# 04_8V_GENERATION.net
KiCad netlist of a schematic drawn in Altium Designer
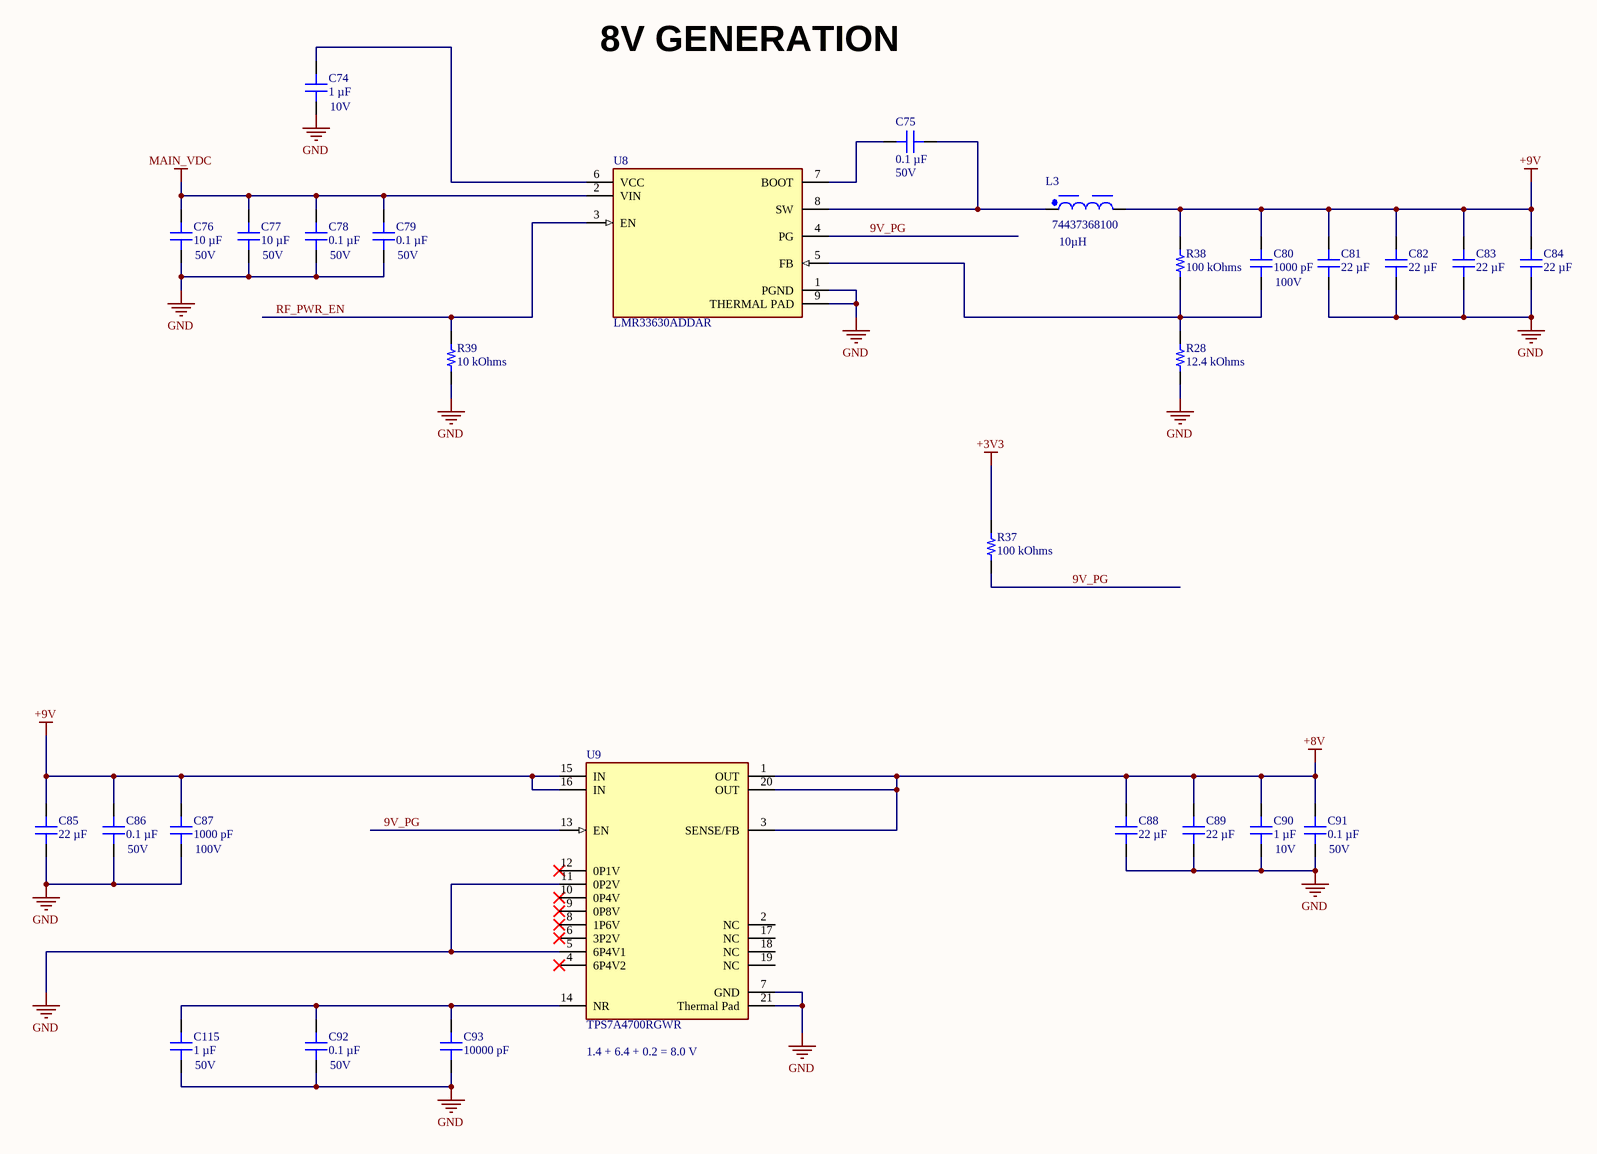
[diagram p0: 04_8V_GENERATION.SchDoc]

(export (version "E")
  (design (tool "Eeschema 10.0.6"))
  (components
    (comp (ref "C74")
      (value "1 µF")
      (footprint "CAP 0402_1005")
      (description "CAP CER 1UF 10V X7S 0402")
      (fields
        (field (name "PART NUMBER") "GRM155C71A105KE11D")
        (field (name "CAPACITANCE") "1 µF")
        (field (name "MANUFACTURER") "Murata Electronics")
        (field (name "VOLTAGE - RATED") "10V")
      )
      (libsource (lib "Celestial Altium Library - altium_library") (part "Capacitor"))
    )
    (comp (ref "C75")
      (value "0.1 µF")
      (footprint "CAP 0402_1005")
      (description "CAP CER 0.1UF 50V X7R 0402")
      (fields
        (field (name "PART NUMBER") "GCM155R71H104KE02J")
        (field (name "CAPACITANCE") "0.1 µF")
        (field (name "MANUFACTURER") "Murata Electronics")
        (field (name "VOLTAGE - RATED") "50V")
      )
      (libsource (lib "Celestial Altium Library - altium_library") (part "Capacitor"))
    )
    (comp (ref "C76")
      (value "10 µF")
      (footprint "CAP 1206_3216 - 0.8MM")
      (description "CAP CER 10UF 50V X7R 1206")
      (fields
        (field (name "PART NUMBER") "CL31B106KBHNNNE")
        (field (name "CAPACITANCE") "10 µF")
        (field (name "MANUFACTURER") "Samsung Electro-Mechanics")
        (field (name "VOLTAGE - RATED") "50V")
      )
      (libsource (lib "Celestial Altium Library - altium_library") (part "Capacitor"))
    )
    (comp (ref "C77")
      (value "10 µF")
      (footprint "CAP 1206_3216 - 0.8MM")
      (description "CAP CER 10UF 50V X7R 1206")
      (fields
        (field (name "PART NUMBER") "CL31B106KBHNNNE")
        (field (name "CAPACITANCE") "10 µF")
        (field (name "MANUFACTURER") "Samsung Electro-Mechanics")
        (field (name "VOLTAGE - RATED") "50V")
      )
      (libsource (lib "Celestial Altium Library - altium_library") (part "Capacitor"))
    )
    (comp (ref "C78")
      (value "0.1 µF")
      (footprint "CAP 0402_1005")
      (description "CAP CER 0.1UF 50V X7R 0402")
      (fields
        (field (name "PART NUMBER") "GCM155R71H104KE02J")
        (field (name "CAPACITANCE") "0.1 µF")
        (field (name "MANUFACTURER") "Murata Electronics")
        (field (name "VOLTAGE - RATED") "50V")
      )
      (libsource (lib "Celestial Altium Library - altium_library") (part "Capacitor"))
    )
    (comp (ref "C79")
      (value "0.1 µF")
      (footprint "CAP 0402_1005")
      (description "CAP CER 0.1UF 50V X7R 0402")
      (fields
        (field (name "PART NUMBER") "GCM155R71H104KE02J")
        (field (name "CAPACITANCE") "0.1 µF")
        (field (name "MANUFACTURER") "Murata Electronics")
        (field (name "VOLTAGE - RATED") "50V")
      )
      (libsource (lib "Celestial Altium Library - altium_library") (part "Capacitor"))
    )
    (comp (ref "C80")
      (value "1000 pF")
      (footprint "CAP 0402_1005")
      (description "CAP CER 1000PF 100V C0G/NP0 0402")
      (fields
        (field (name "PART NUMBER") "C0402H102J1GAC7867")
        (field (name "CAPACITANCE") "1000 pF")
        (field (name "MANUFACTURER") "KEMET")
        (field (name "VOLTAGE - RATED") "100V")
      )
      (libsource (lib "Celestial Altium Library - altium_library") (part "Capacitor"))
    )
    (comp (ref "C81")
      (value "22 µF")
      (footprint "CAP 0805_2012")
      (description "CAP CER 22UF 16V X5R 0805")
      (fields
        (field (name "PART NUMBER") "CL21A226KOQNNNE")
        (field (name "CAPACITANCE") "22 µF")
        (field (name "MANUFACTURER") "Samsung Electro-Mechanics")
      )
      (libsource (lib "Celestial Altium Library - altium_library") (part "Capacitor"))
    )
    (comp (ref "C82")
      (value "22 µF")
      (footprint "CAP 0805_2012")
      (description "CAP CER 22UF 16V X5R 0805")
      (fields
        (field (name "PART NUMBER") "CL21A226KOQNNNE")
        (field (name "CAPACITANCE") "22 µF")
        (field (name "MANUFACTURER") "Samsung Electro-Mechanics")
      )
      (libsource (lib "Celestial Altium Library - altium_library") (part "Capacitor"))
    )
    (comp (ref "C83")
      (value "22 µF")
      (footprint "CAP 0805_2012")
      (description "CAP CER 22UF 16V X5R 0805")
      (fields
        (field (name "PART NUMBER") "CL21A226KOQNNNE")
        (field (name "CAPACITANCE") "22 µF")
        (field (name "MANUFACTURER") "Samsung Electro-Mechanics")
      )
      (libsource (lib "Celestial Altium Library - altium_library") (part "Capacitor"))
    )
    (comp (ref "C84")
      (value "22 µF")
      (footprint "CAP 0805_2012")
      (description "CAP CER 22UF 16V X5R 0805")
      (fields
        (field (name "PART NUMBER") "CL21A226KOQNNNE")
        (field (name "CAPACITANCE") "22 µF")
        (field (name "MANUFACTURER") "Samsung Electro-Mechanics")
      )
      (libsource (lib "Celestial Altium Library - altium_library") (part "Capacitor"))
    )
    (comp (ref "C85")
      (value "22 µF")
      (footprint "CAP 0805_2012")
      (description "CAP CER 22UF 16V X5R 0805")
      (fields
        (field (name "PART NUMBER") "CL21A226KOQNNNE")
        (field (name "CAPACITANCE") "22 µF")
        (field (name "MANUFACTURER") "Samsung Electro-Mechanics")
      )
      (libsource (lib "Celestial Altium Library - altium_library") (part "Capacitor"))
    )
    (comp (ref "C86")
      (value "0.1 µF")
      (footprint "CAP 0402_1005")
      (description "CAP CER 0.1UF 50V X7R 0402")
      (fields
        (field (name "PART NUMBER") "GCM155R71H104KE02J")
        (field (name "CAPACITANCE") "0.1 µF")
        (field (name "MANUFACTURER") "Murata Electronics")
        (field (name "VOLTAGE - RATED") "50V")
      )
      (libsource (lib "Celestial Altium Library - altium_library") (part "Capacitor"))
    )
    (comp (ref "C87")
      (value "1000 pF")
      (footprint "CAP 0402_1005")
      (description "CAP CER 1000PF 100V C0G/NP0 0402")
      (fields
        (field (name "PART NUMBER") "C0402H102J1GAC7867")
        (field (name "CAPACITANCE") "1000 pF")
        (field (name "MANUFACTURER") "KEMET")
        (field (name "VOLTAGE - RATED") "100V")
      )
      (libsource (lib "Celestial Altium Library - altium_library") (part "Capacitor"))
    )
    (comp (ref "C88")
      (value "22 µF")
      (footprint "CAP 0805_2012")
      (description "CAP CER 22UF 16V X5R 0805")
      (fields
        (field (name "PART NUMBER") "CL21A226KOQNNNE")
        (field (name "CAPACITANCE") "22 µF")
        (field (name "MANUFACTURER") "Samsung Electro-Mechanics")
      )
      (libsource (lib "Celestial Altium Library - altium_library") (part "Capacitor"))
    )
    (comp (ref "C89")
      (value "22 µF")
      (footprint "CAP 0805_2012")
      (description "CAP CER 22UF 16V X5R 0805")
      (fields
        (field (name "PART NUMBER") "CL21A226KOQNNNE")
        (field (name "CAPACITANCE") "22 µF")
        (field (name "MANUFACTURER") "Samsung Electro-Mechanics")
      )
      (libsource (lib "Celestial Altium Library - altium_library") (part "Capacitor"))
    )
    (comp (ref "C90")
      (value "1 µF")
      (footprint "CAP 0402_1005")
      (description "CAP CER 1UF 10V X7S 0402")
      (fields
        (field (name "PART NUMBER") "GRM155C71A105KE11D")
        (field (name "CAPACITANCE") "1 µF")
        (field (name "MANUFACTURER") "Murata Electronics")
        (field (name "VOLTAGE - RATED") "10V")
      )
      (libsource (lib "Celestial Altium Library - altium_library") (part "Capacitor"))
    )
    (comp (ref "C91")
      (value "0.1 µF")
      (footprint "CAP 0402_1005")
      (description "CAP CER 0.1UF 50V X7R 0402")
      (fields
        (field (name "PART NUMBER") "GCM155R71H104KE02J")
        (field (name "CAPACITANCE") "0.1 µF")
        (field (name "MANUFACTURER") "Murata Electronics")
        (field (name "VOLTAGE - RATED") "50V")
      )
      (libsource (lib "Celestial Altium Library - altium_library") (part "Capacitor"))
    )
    (comp (ref "C92")
      (value "0.1 µF")
      (footprint "CAP 0402_1005")
      (description "CAP CER 0.1UF 50V X7R 0402")
      (fields
        (field (name "PART NUMBER") "GCM155R71H104KE02J")
        (field (name "CAPACITANCE") "0.1 µF")
        (field (name "MANUFACTURER") "Murata Electronics")
        (field (name "VOLTAGE - RATED") "50V")
      )
      (libsource (lib "Celestial Altium Library - altium_library") (part "Capacitor"))
    )
    (comp (ref "C93")
      (value "10000 pF")
      (footprint "CAP 0402_1005")
      (description "CAP CER 10000PF 50V X7R 0402")
      (fields
        (field (name "PART NUMBER") "AC0402KPX7R9BB103")
        (field (name "CAPACITANCE") "10000 pF")
        (field (name "MANUFACTURER") "Yageo")
      )
      (libsource (lib "Celestial Altium Library - altium_library") (part "Capacitor"))
    )
    (comp (ref "C115")
      (value "1 µF")
      (footprint "CAP 0805_2012")
      (description "CAP CER 1UF 50V X7R 0805")
      (fields
        (field (name "PART NUMBER") "UMF212B7105KGHT")
        (field (name "CAPACITANCE") "1 µF")
        (field (name "MANUFACTURER") "Taiyo Yuden")
        (field (name "VOLTAGE - RATED") "50V")
      )
      (libsource (lib "Celestial Altium Library - altium_library") (part "Capacitor"))
    )
    (comp (ref "L3")
      (value "74437368100")
      (footprint "WE-LHMI_1040")
      (description "We-lhmi; 10000NH; Composite Iron Multilayer SMD Induc., 1040 Case; .012GHZ 5.2A")
      (fields (field (name "INDUCTANCE") "10µH") (field (name "TOLERANCE") "20%"))
      (libsource (lib "Altium Content Vault") (part "Inductor - 2"))
    )
    (comp (ref "R28")
      (value "12.4 kOhms")
      (footprint "RES 0402_1005")
      (description "RES SMD 12.4K OHM 1% 1/16W 0402")
      (fields (field (name "PART NUMBER") "RT0402FRE0712K4L") (field (name "MANUFACTURER") "Yageo"))
      (libsource (lib "Celestial Altium Library - altium_library") (part "Resistor"))
    )
    (comp (ref "R37")
      (value "100 kOhms")
      (footprint "RES 0402_1005")
      (description "RES SMD 100K OHM 1% 1/16W 0402")
      (fields (field (name "PART NUMBER") "AC0402FR-07100KL") (field (name "MANUFACTURER") "Yageo"))
      (libsource (lib "Celestial Altium Library - altium_library") (part "Resistor"))
    )
    (comp (ref "R38")
      (value "100 kOhms")
      (footprint "RES 0402_1005")
      (description "RES 100K OHM 1% 1/16W 0402")
      (fields (field (name "PART NUMBER") "RC0402FR-13100KL") (field (name "MANUFACTURER") "Yageo"))
      (libsource (lib "Celestial Altium Library - altium_library") (part "Resistor"))
    )
    (comp (ref "R39")
      (value "10 kOhms")
      (footprint "RES 0402_1005")
      (description "RES 10K OHM 1% 1/16W 0402")
      (fields (field (name "PART NUMBER") "RC0402FR-0710KL") (field (name "MANUFACTURER") "Yageo"))
      (libsource (lib "Celestial Altium Library - altium_library") (part "Resistor"))
    )
    (comp (ref "U8")
      (value "LMR33630ADDAR")
      (footprint "FP-DDA0008J-MFG")
      (description "IC REG BUCK ADJUSTABLE 3A 8SOPWR")
      (libsource (lib "Altium Content Vault") (part "6a354f5098e7f60ae670b755afcc2ec"))
    )
    (comp (ref "U9")
      (value "TPS7A4700RGWR")
      (footprint "FP-RGW0020A-MFG")
      (description "IC REG LINEAR POS ADJ 1A 20VQFN")
      (fields
        (field (name "OCTOPART") "https://octopart.com/tps7a4700rgwr-texas+instruments-21221956")
        (field (name "MANUFACTURER") "Texas Instruments")
      )
      (libsource (lib "Altium Content Vault") (part "8e99b082ac9f85253ef2256b190b767"))
    )
  )
  (nets
    (net (code "1") (name "+3V3") (class "Default")
      (node (ref "R37") (pin "2") (pinfunction "2_2") (pintype "passive"))
    )
    (net (code "2") (name "+8V") (class "Default")
      (node (ref "C88") (pin "2") (pinfunction "2_2") (pintype "passive"))
      (node (ref "C89") (pin "2") (pinfunction "2_2") (pintype "passive"))
      (node (ref "C90") (pin "1") (pinfunction "1_1") (pintype "passive"))
      (node (ref "C91") (pin "2") (pinfunction "2_2") (pintype "passive"))
      (node (ref "U9") (pin "1") (pinfunction "OUT_1") (pintype "power_in"))
      (node (ref "U9") (pin "20") (pinfunction "OUT_20") (pintype "power_in"))
      (node (ref "U9") (pin "3") (pinfunction "SENSE/FB_3") (pintype "passive"))
    )
    (net (code "3") (name "+9V") (class "Default")
      (node (ref "C80") (pin "2") (pinfunction "2_2") (pintype "passive"))
      (node (ref "C81") (pin "2") (pinfunction "2_2") (pintype "passive"))
      (node (ref "C82") (pin "2") (pinfunction "2_2") (pintype "passive"))
      (node (ref "C83") (pin "2") (pinfunction "2_2") (pintype "passive"))
      (node (ref "C84") (pin "2") (pinfunction "2_2") (pintype "passive"))
      (node (ref "C85") (pin "2") (pinfunction "2_2") (pintype "passive"))
      (node (ref "C86") (pin "2") (pinfunction "2_2") (pintype "passive"))
      (node (ref "C87") (pin "2") (pinfunction "2_2") (pintype "passive"))
      (node (ref "L3") (pin "2") (pinfunction "2_2") (pintype "passive"))
      (node (ref "R38") (pin "2") (pinfunction "2_2") (pintype "passive"))
      (node (ref "U9") (pin "15") (pinfunction "IN_15") (pintype "power_in"))
      (node (ref "U9") (pin "16") (pinfunction "IN_16") (pintype "power_in"))
    )
    (net (code "4") (name "/9V_PG") (class "Default")
      (node (ref "R37") (pin "1") (pinfunction "1_1") (pintype "passive"))
      (node (ref "U8") (pin "4") (pinfunction "PG_4") (pintype "open_collector"))
      (node (ref "U9") (pin "13") (pinfunction "EN_13") (pintype "input"))
    )
    (net (code "5") (name "/RF_PWR_EN") (class "Default")
      (node (ref "R39") (pin "2") (pinfunction "2_2") (pintype "passive"))
      (node (ref "U8") (pin "3") (pinfunction "EN_3") (pintype "input"))
    )
    (net (code "6") (name "GND") (class "Default")
      (node (ref "C115") (pin "1") (pinfunction "1_1") (pintype "passive"))
      (node (ref "C74") (pin "2") (pinfunction "2_2") (pintype "passive"))
      (node (ref "C76") (pin "1") (pinfunction "1_1") (pintype "passive"))
      (node (ref "C77") (pin "1") (pinfunction "1_1") (pintype "passive"))
      (node (ref "C78") (pin "1") (pinfunction "1_1") (pintype "passive"))
      (node (ref "C79") (pin "1") (pinfunction "1_1") (pintype "passive"))
      (node (ref "C81") (pin "1") (pinfunction "1_1") (pintype "passive"))
      (node (ref "C82") (pin "1") (pinfunction "1_1") (pintype "passive"))
      (node (ref "C83") (pin "1") (pinfunction "1_1") (pintype "passive"))
      (node (ref "C84") (pin "1") (pinfunction "1_1") (pintype "passive"))
      (node (ref "C85") (pin "1") (pinfunction "1_1") (pintype "passive"))
      (node (ref "C86") (pin "1") (pinfunction "1_1") (pintype "passive"))
      (node (ref "C87") (pin "1") (pinfunction "1_1") (pintype "passive"))
      (node (ref "C88") (pin "1") (pinfunction "1_1") (pintype "passive"))
      (node (ref "C89") (pin "1") (pinfunction "1_1") (pintype "passive"))
      (node (ref "C90") (pin "2") (pinfunction "2_2") (pintype "passive"))
      (node (ref "C91") (pin "1") (pinfunction "1_1") (pintype "passive"))
      (node (ref "C92") (pin "1") (pinfunction "1_1") (pintype "passive"))
      (node (ref "C93") (pin "1") (pinfunction "1_1") (pintype "passive"))
      (node (ref "R28") (pin "1") (pinfunction "1_1") (pintype "passive"))
      (node (ref "R39") (pin "1") (pinfunction "1_1") (pintype "passive"))
      (node (ref "U8") (pin "1") (pinfunction "PGND_1") (pintype "power_in"))
      (node (ref "U8") (pin "9") (pinfunction "THERMAL_PAD_9") (pintype "passive"))
      (node (ref "U9") (pin "11") (pinfunction "0P2V_11") (pintype "passive"))
      (node (ref "U9") (pin "21") (pinfunction "Thermal_Pad_21") (pintype "power_in"))
      (node (ref "U9") (pin "5") (pinfunction "6P4V1_5") (pintype "passive"))
      (node (ref "U9") (pin "7") (pinfunction "GND_7") (pintype "power_in"))
    )
    (net (code "7") (name "MAIN_VDC") (class "Default")
      (node (ref "C76") (pin "2") (pinfunction "2_2") (pintype "passive"))
      (node (ref "C77") (pin "2") (pinfunction "2_2") (pintype "passive"))
      (node (ref "C78") (pin "2") (pinfunction "2_2") (pintype "passive"))
      (node (ref "C79") (pin "2") (pinfunction "2_2") (pintype "passive"))
      (node (ref "U8") (pin "2") (pinfunction "VIN_2") (pintype "power_in"))
    )
    (net (code "8") (name "Net-(U8-BOOT)") (class "Default")
      (node (ref "C75") (pin "2") (pinfunction "2_2") (pintype "passive"))
      (node (ref "U8") (pin "7") (pinfunction "BOOT_7") (pintype "passive"))
    )
    (net (code "9") (name "Net-(U8-FB)") (class "Default")
      (node (ref "C80") (pin "1") (pinfunction "1_1") (pintype "passive"))
      (node (ref "R28") (pin "2") (pinfunction "2_2") (pintype "passive"))
      (node (ref "R38") (pin "1") (pinfunction "1_1") (pintype "passive"))
      (node (ref "U8") (pin "5") (pinfunction "FB_5") (pintype "input"))
    )
    (net (code "10") (name "Net-(U8-SW)") (class "Default")
      (node (ref "C75") (pin "1") (pinfunction "1_1") (pintype "passive"))
      (node (ref "L3") (pin "1") (pinfunction "1_1") (pintype "passive"))
      (node (ref "U8") (pin "8") (pinfunction "SW_8") (pintype "passive"))
    )
    (net (code "11") (name "Net-(U8-VCC)") (class "Default")
      (node (ref "C74") (pin "1") (pinfunction "1_1") (pintype "passive"))
      (node (ref "U8") (pin "6") (pinfunction "VCC_6") (pintype "power_in"))
    )
    (net (code "12") (name "Net-(U9-NR)") (class "Default")
      (node (ref "C115") (pin "2") (pinfunction "2_2") (pintype "passive"))
      (node (ref "C92") (pin "2") (pinfunction "2_2") (pintype "passive"))
      (node (ref "C93") (pin "2") (pinfunction "2_2") (pintype "passive"))
      (node (ref "U9") (pin "14") (pinfunction "NR_14") (pintype "passive"))
    )
    (net (code "13") (name "unconnected-(U9-0P1V-Pad12)") (class "Default")
      (node (ref "U9") (pin "12") (pinfunction "0P1V_12") (pintype "passive+no_connect"))
    )
    (net (code "14") (name "unconnected-(U9-0P4V-Pad10)") (class "Default")
      (node (ref "U9") (pin "10") (pinfunction "0P4V_10") (pintype "passive+no_connect"))
    )
    (net (code "15") (name "unconnected-(U9-0P8V-Pad9)") (class "Default")
      (node (ref "U9") (pin "9") (pinfunction "0P8V_9") (pintype "passive+no_connect"))
    )
    (net (code "16") (name "unconnected-(U9-1P6V-Pad8)") (class "Default")
      (node (ref "U9") (pin "8") (pinfunction "1P6V_8") (pintype "passive+no_connect"))
    )
    (net (code "17") (name "unconnected-(U9-3P2V-Pad6)") (class "Default")
      (node (ref "U9") (pin "6") (pinfunction "3P2V_6") (pintype "passive+no_connect"))
    )
    (net (code "18") (name "unconnected-(U9-6P4V2-Pad4)") (class "Default")
      (node (ref "U9") (pin "4") (pinfunction "6P4V2_4") (pintype "passive+no_connect"))
    )
    (net (code "19") (name "unconnected-(U9-NC-Pad2)") (class "Default")
      (node (ref "U9") (pin "2") (pinfunction "NC_2") (pintype "passive"))
    )
    (net (code "20") (name "unconnected-(U9-NC-Pad17)") (class "Default")
      (node (ref "U9") (pin "17") (pinfunction "NC_17") (pintype "passive"))
    )
    (net (code "21") (name "unconnected-(U9-NC-Pad18)") (class "Default")
      (node (ref "U9") (pin "18") (pinfunction "NC_18") (pintype "passive"))
    )
    (net (code "22") (name "unconnected-(U9-NC-Pad19)") (class "Default")
      (node (ref "U9") (pin "19") (pinfunction "NC_19") (pintype "passive"))
    )
  )
)
